# MCU.net
KiCad netlist of a schematic drawn in Altium Designer
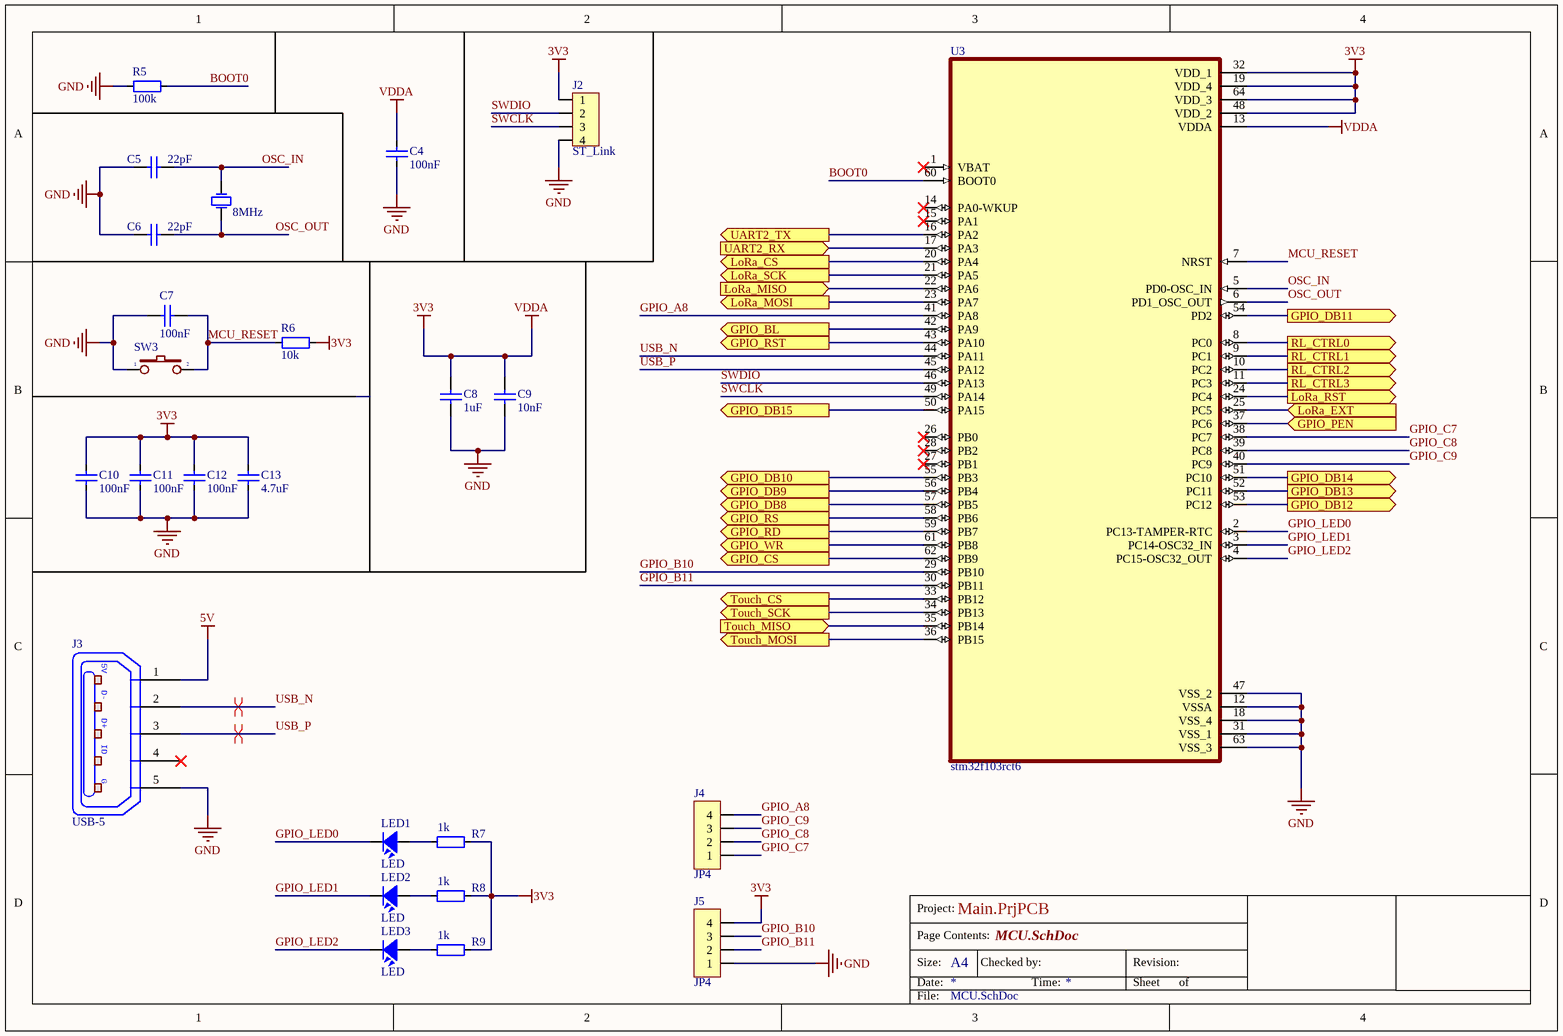
[diagram p0: MCU.SchDoc]

(export (version "E")
  (design (tool "Eeschema 10.0.6"))
  (components
    (comp (ref "C4")
      (value "100nF")
      (footprint "CAP_0805")
      (description "Capacitor")
      (fields (field (name "PUBLISHER") "Altium Limited"))
      (libsource (lib "") (part "CapSMD_1"))
    )
    (comp (ref "C5")
      (value "22pF")
      (footprint "CAP_0805")
      (description "Capacitor")
      (fields (field (name "PUBLISHER") "Altium Limited"))
      (libsource (lib "My Library") (part "CapSMD"))
    )
    (comp (ref "C6")
      (value "22pF")
      (footprint "CAP_0805")
      (description "Capacitor")
      (fields (field (name "PUBLISHER") "Altium Limited"))
      (libsource (lib "My Library") (part "CapSMD"))
    )
    (comp (ref "C7")
      (value "100nF")
      (footprint "CAP_0805")
      (description "Capacitor")
      (fields (field (name "PUBLISHER") "Altium Limited"))
      (libsource (lib "My Library") (part "CapSMD"))
    )
    (comp (ref "C8")
      (value "1uF")
      (footprint "CAP_0805")
      (description "Capacitor")
      (fields (field (name "PUBLISHER") "Altium Limited"))
      (libsource (lib "My Library") (part "CapSMD"))
    )
    (comp (ref "C9")
      (value "10nF")
      (footprint "CAP_0805")
      (description "Capacitor")
      (fields (field (name "PUBLISHER") "Altium Limited"))
      (libsource (lib "My Library") (part "CapSMD"))
    )
    (comp (ref "C10")
      (value "100nF")
      (footprint "CAP_0805")
      (description "Capacitor")
      (fields (field (name "PUBLISHER") "Altium Limited"))
      (libsource (lib "") (part "CapSMD_1"))
    )
    (comp (ref "C11")
      (value "100nF")
      (footprint "CAP_0805")
      (description "Capacitor")
      (fields (field (name "PUBLISHER") "Altium Limited"))
      (libsource (lib "") (part "CapSMD_1"))
    )
    (comp (ref "C12")
      (value "100nF")
      (footprint "CAP_0805")
      (description "Capacitor")
      (fields (field (name "PUBLISHER") "Altium Limited"))
      (libsource (lib "") (part "CapSMD_1"))
    )
    (comp (ref "C13")
      (value "4.7uF")
      (footprint "CAP_0805")
      (description "Capacitor")
      (fields (field (name "PUBLISHER") "Altium Limited"))
      (libsource (lib "") (part "CapSMD_1"))
    )
    (comp (ref "J2")
      (value "ST_Link")
      (footprint "JP4-C1T")
      (description "Header IDC, 4 x 1 Pin Vertical 2.54mm Pitch (Non-Boxed, Male)")
      (fields
        (field (name "MANUFACTURER") "Würth Elektronik eiSos GmbH")
        (field (name "PARTNO") "613002143121")
        (field (name "CREATED BY") "Karrer Zheng")
      )
      (libsource (lib "My Library") (part "Header4"))
    )
    (comp (ref "J3")
      (value "USB-5")
      (footprint "USB-M1")
      (fields
        (field (name "MANUFACTURER") "FCI")
        (field (name "MANUFACTURER PART NUMBER") "10118193-0001LF")
        (field (name ".CREATOR") "MM")
        (field (name ".CHECKED PCB") "RF")
        (field (name ".CHECKED SCH") "MM")
      )
      (libsource (lib "My Library") (part "USB-5"))
    )
    (comp (ref "J4")
      (value "JP4")
      (footprint "JP4-C1T")
      (description "WR-PHD 2.54 mm Angled Socket Header")
      (fields
        (field (name "MANUFACTURER") "Würth Elektronik eiSos GmbH")
        (field (name "PARTNO") "613004143121")
        (field (name "CREATED BY") "Karrer Zheng")
      )
      (libsource (lib "My Library") (part "JP4"))
    )
    (comp (ref "J5")
      (value "JP4")
      (footprint "JP4-C1T")
      (description "WR-PHD 2.54 mm Angled Socket Header")
      (fields
        (field (name "MANUFACTURER") "Würth Elektronik eiSos GmbH")
        (field (name "PARTNO") "613004143121")
        (field (name "CREATED BY") "Karrer Zheng")
      )
      (libsource (lib "My Library") (part "JP4"))
    )
    (comp (ref "LED1")
      (value "LED")
      (footprint "LED-0805-Red")
      (description "LED Single colour Green and Red")
      (libsource (lib "My Library") (part "LED"))
    )
    (comp (ref "LED2")
      (value "LED")
      (footprint "LED-0805-Green")
      (description "LED Single colour Green and Red")
      (libsource (lib "My Library") (part "LED"))
    )
    (comp (ref "LED3")
      (value "LED")
      (footprint "LED-0805-Blue")
      (description "LED Single colour Green and Red")
      (libsource (lib "My Library") (part "LED"))
    )
    (comp (ref "R5")
      (value "100k")
      (footprint "RES-SMD-0805")
      (description "Resistor")
      (fields
        (field (name "MANUFACTURER") "Generic Components")
        (field (name "PUBLISHER") "Altium Hobart Technology Centre")
      )
      (libsource (lib "My Library") (part "Resistor - SMD"))
    )
    (comp (ref "R6")
      (value "10k")
      (footprint "RES-SMD-0805")
      (description "Resistor")
      (fields
        (field (name "MANUFACTURER") "Generic Components")
        (field (name "PUBLISHER") "Altium Hobart Technology Centre")
      )
      (libsource (lib "My Library") (part "Resistor - SMD"))
    )
    (comp (ref "R7")
      (value "1k")
      (footprint "RES-SMD-0805")
      (description "Resistor")
      (fields
        (field (name "MANUFACTURER") "Generic Components")
        (field (name "PUBLISHER") "Altium Hobart Technology Centre")
      )
      (libsource (lib "My Library") (part "Resistor - SMD"))
    )
    (comp (ref "R8")
      (value "1k")
      (footprint "RES-SMD-0805")
      (description "Resistor")
      (fields
        (field (name "MANUFACTURER") "Generic Components")
        (field (name "PUBLISHER") "Altium Hobart Technology Centre")
      )
      (libsource (lib "My Library") (part "Resistor - SMD"))
    )
    (comp (ref "R9")
      (value "1k")
      (footprint "RES-SMD-0805")
      (description "Resistor")
      (fields
        (field (name "MANUFACTURER") "Generic Components")
        (field (name "PUBLISHER") "Altium Hobart Technology Centre")
      )
      (libsource (lib "My Library") (part "Resistor - SMD"))
    )
    (comp (ref "SW3")
      (value "SW")
      (footprint "SW2")
      (description "Switch button 2 pin")
      (libsource (lib "My Library") (part "SW2"))
    )
    (comp (ref "U3")
      (value "stm32f103rct6")
      (footprint "QFP50P1200X1200X160-64N")
      (libsource (lib "My Library") (part "stm32f103rct6"))
    )
    (comp (ref "Y1")
      (value "8MHz")
      (footprint "XTAL")
      (description "Crystal Oscillator")
      (fields (field (name "PUBLISHER") "Altium Limited"))
      (libsource (lib "My Library") (part "XTAL"))
    )
  )
  (nets
    (net (code "1") (name "/BOOT0") (class "Default")
      (node (ref "R5") (pin "1") (pinfunction "1_1") (pintype "passive"))
      (node (ref "U3") (pin "60") (pinfunction "BOOT0_60") (pintype "input"))
    )
    (net (code "2") (name "/GPIO_A8") (class "Default")
      (node (ref "J4") (pin "4") (pinfunction "4_4") (pintype "passive"))
      (node (ref "U3") (pin "41") (pinfunction "PA8_41") (pintype "bidirectional"))
    )
    (net (code "3") (name "/GPIO_B10") (class "Default")
      (node (ref "J5") (pin "3") (pinfunction "3_3") (pintype "passive"))
      (node (ref "U3") (pin "29") (pinfunction "PB10_29") (pintype "bidirectional"))
    )
    (net (code "4") (name "/GPIO_B11") (class "Default")
      (node (ref "J5") (pin "2") (pinfunction "2_2") (pintype "passive"))
      (node (ref "U3") (pin "30") (pinfunction "PB11_30") (pintype "bidirectional"))
    )
    (net (code "5") (name "/GPIO_BL") (class "Default")
      (node (ref "U3") (pin "42") (pinfunction "PA9_42") (pintype "bidirectional"))
    )
    (net (code "6") (name "/GPIO_C7") (class "Default")
      (node (ref "J4") (pin "1") (pinfunction "1_1") (pintype "passive"))
      (node (ref "U3") (pin "38") (pinfunction "PC7_38") (pintype "bidirectional"))
    )
    (net (code "7") (name "/GPIO_C8") (class "Default")
      (node (ref "J4") (pin "2") (pinfunction "2_2") (pintype "passive"))
      (node (ref "U3") (pin "39") (pinfunction "PC8_39") (pintype "bidirectional"))
    )
    (net (code "8") (name "/GPIO_C9") (class "Default")
      (node (ref "J4") (pin "3") (pinfunction "3_3") (pintype "passive"))
      (node (ref "U3") (pin "40") (pinfunction "PC9_40") (pintype "bidirectional"))
    )
    (net (code "9") (name "/GPIO_CS") (class "Default")
      (node (ref "U3") (pin "62") (pinfunction "PB9_62") (pintype "bidirectional"))
    )
    (net (code "10") (name "/GPIO_DB8") (class "Default")
      (node (ref "U3") (pin "57") (pinfunction "PB5_57") (pintype "bidirectional"))
    )
    (net (code "11") (name "/GPIO_DB9") (class "Default")
      (node (ref "U3") (pin "56") (pinfunction "PB4_56") (pintype "bidirectional"))
    )
    (net (code "12") (name "/GPIO_DB10") (class "Default")
      (node (ref "U3") (pin "55") (pinfunction "PB3_55") (pintype "bidirectional"))
    )
    (net (code "13") (name "/GPIO_DB11") (class "Default")
      (node (ref "U3") (pin "54") (pinfunction "PD2_54") (pintype "bidirectional"))
    )
    (net (code "14") (name "/GPIO_DB12") (class "Default")
      (node (ref "U3") (pin "53") (pinfunction "PC12_53") (pintype "bidirectional"))
    )
    (net (code "15") (name "/GPIO_DB13") (class "Default")
      (node (ref "U3") (pin "52") (pinfunction "PC11_52") (pintype "bidirectional"))
    )
    (net (code "16") (name "/GPIO_DB14") (class "Default")
      (node (ref "U3") (pin "51") (pinfunction "PC10_51") (pintype "bidirectional"))
    )
    (net (code "17") (name "/GPIO_DB15") (class "Default")
      (node (ref "U3") (pin "50") (pinfunction "PA15_50") (pintype "bidirectional"))
    )
    (net (code "18") (name "/GPIO_LED0") (class "Default")
      (node (ref "LED1") (pin "2") (pinfunction "2_2") (pintype "passive"))
      (node (ref "U3") (pin "2") (pinfunction "PC13-TAMPER-RTC_2") (pintype "bidirectional"))
    )
    (net (code "19") (name "/GPIO_LED1") (class "Default")
      (node (ref "LED2") (pin "2") (pinfunction "2_2") (pintype "passive"))
      (node (ref "U3") (pin "3") (pinfunction "PC14-OSC32_IN_3") (pintype "bidirectional"))
    )
    (net (code "20") (name "/GPIO_LED2") (class "Default")
      (node (ref "LED3") (pin "2") (pinfunction "2_2") (pintype "passive"))
      (node (ref "U3") (pin "4") (pinfunction "PC15-OSC32_OUT_4") (pintype "bidirectional"))
    )
    (net (code "21") (name "/GPIO_PEN") (class "Default")
      (node (ref "U3") (pin "37") (pinfunction "PC6_37") (pintype "bidirectional"))
    )
    (net (code "22") (name "/GPIO_RD") (class "Default")
      (node (ref "U3") (pin "59") (pinfunction "PB7_59") (pintype "bidirectional"))
    )
    (net (code "23") (name "/GPIO_RS") (class "Default")
      (node (ref "U3") (pin "58") (pinfunction "PB6_58") (pintype "bidirectional"))
    )
    (net (code "24") (name "/GPIO_RST") (class "Default")
      (node (ref "U3") (pin "43") (pinfunction "PA10_43") (pintype "bidirectional"))
    )
    (net (code "25") (name "/GPIO_WR") (class "Default")
      (node (ref "U3") (pin "61") (pinfunction "PB8_61") (pintype "bidirectional"))
    )
    (net (code "26") (name "/LoRa_CS") (class "Default")
      (node (ref "U3") (pin "20") (pinfunction "PA4_20") (pintype "bidirectional"))
    )
    (net (code "27") (name "/LoRa_EXT") (class "Default")
      (node (ref "U3") (pin "25") (pinfunction "PC5_25") (pintype "bidirectional"))
    )
    (net (code "28") (name "/LoRa_MISO") (class "Default")
      (node (ref "U3") (pin "22") (pinfunction "PA6_22") (pintype "bidirectional"))
    )
    (net (code "29") (name "/LoRa_MOSI") (class "Default")
      (node (ref "U3") (pin "23") (pinfunction "PA7_23") (pintype "bidirectional"))
    )
    (net (code "30") (name "/LoRa_RST") (class "Default")
      (node (ref "U3") (pin "24") (pinfunction "PC4_24") (pintype "bidirectional"))
    )
    (net (code "31") (name "/LoRa_SCK") (class "Default")
      (node (ref "U3") (pin "21") (pinfunction "PA5_21") (pintype "bidirectional"))
    )
    (net (code "32") (name "/MCU_RESET") (class "Default")
      (node (ref "C7") (pin "2") (pinfunction "2_2") (pintype "passive"))
      (node (ref "R6") (pin "2") (pinfunction "2_2") (pintype "passive"))
      (node (ref "SW3") (pin "2") (pinfunction "2_2") (pintype "passive"))
      (node (ref "U3") (pin "7") (pinfunction "NRST_7") (pintype "input"))
    )
    (net (code "33") (name "/OSC_IN") (class "Default")
      (node (ref "C5") (pin "2") (pinfunction "2_2") (pintype "passive"))
      (node (ref "U3") (pin "5") (pinfunction "PD0-OSC_IN_5") (pintype "input"))
      (node (ref "Y1") (pin "1") (pinfunction "OSC1_1") (pintype "passive"))
    )
    (net (code "34") (name "/OSC_OUT") (class "Default")
      (node (ref "C6") (pin "2") (pinfunction "2_2") (pintype "passive"))
      (node (ref "U3") (pin "6") (pinfunction "PD1_OSC_OUT_6") (pintype "output"))
      (node (ref "Y1") (pin "2") (pinfunction "OSC2_2") (pintype "passive"))
    )
    (net (code "35") (name "/RL_CTRL0") (class "Default")
      (node (ref "U3") (pin "8") (pinfunction "PC0_8") (pintype "bidirectional"))
    )
    (net (code "36") (name "/RL_CTRL1") (class "Default")
      (node (ref "U3") (pin "9") (pinfunction "PC1_9") (pintype "bidirectional"))
    )
    (net (code "37") (name "/RL_CTRL2") (class "Default")
      (node (ref "U3") (pin "10") (pinfunction "PC2_10") (pintype "bidirectional"))
    )
    (net (code "38") (name "/RL_CTRL3") (class "Default")
      (node (ref "U3") (pin "11") (pinfunction "PC3_11") (pintype "bidirectional"))
    )
    (net (code "39") (name "/SWCLK") (class "Default")
      (node (ref "J2") (pin "3") (pinfunction "3_3") (pintype "passive"))
      (node (ref "U3") (pin "49") (pinfunction "PA14_49") (pintype "bidirectional"))
    )
    (net (code "40") (name "/SWDIO") (class "Default")
      (node (ref "J2") (pin "2") (pinfunction "2_2") (pintype "passive"))
      (node (ref "U3") (pin "46") (pinfunction "PA13_46") (pintype "bidirectional"))
    )
    (net (code "41") (name "/Touch_CS") (class "Default")
      (node (ref "U3") (pin "33") (pinfunction "PB12_33") (pintype "bidirectional"))
    )
    (net (code "42") (name "/Touch_MISO") (class "Default")
      (node (ref "U3") (pin "35") (pinfunction "PB14_35") (pintype "bidirectional"))
    )
    (net (code "43") (name "/Touch_MOSI") (class "Default")
      (node (ref "U3") (pin "36") (pinfunction "PB15_36") (pintype "bidirectional"))
    )
    (net (code "44") (name "/Touch_SCK") (class "Default")
      (node (ref "U3") (pin "34") (pinfunction "PB13_34") (pintype "bidirectional"))
    )
    (net (code "45") (name "/UART2_RX") (class "Default")
      (node (ref "U3") (pin "17") (pinfunction "PA3_17") (pintype "bidirectional"))
    )
    (net (code "46") (name "/UART2_TX") (class "Default")
      (node (ref "U3") (pin "16") (pinfunction "PA2_16") (pintype "bidirectional"))
    )
    (net (code "47") (name "/USB_N") (class "Default")
      (node (ref "J3") (pin "2") (pinfunction "P2_2") (pintype "passive"))
      (node (ref "U3") (pin "44") (pinfunction "PA11_44") (pintype "bidirectional"))
    )
    (net (code "48") (name "/USB_P") (class "Default")
      (node (ref "J3") (pin "3") (pinfunction "P3_3") (pintype "passive"))
      (node (ref "U3") (pin "45") (pinfunction "PA12_45") (pintype "bidirectional"))
    )
    (net (code "49") (name "3V3") (class "Default")
      (node (ref "C10") (pin "2") (pinfunction "2_2") (pintype "passive"))
      (node (ref "C11") (pin "2") (pinfunction "2_2") (pintype "passive"))
      (node (ref "C12") (pin "2") (pinfunction "2_2") (pintype "passive"))
      (node (ref "C13") (pin "2") (pinfunction "2_2") (pintype "passive"))
      (node (ref "C4") (pin "2") (pinfunction "2_2") (pintype "passive"))
      (node (ref "C8") (pin "2") (pinfunction "2_2") (pintype "passive"))
      (node (ref "C9") (pin "2") (pinfunction "2_2") (pintype "passive"))
      (node (ref "J2") (pin "1") (pinfunction "1_1") (pintype "passive"))
      (node (ref "J5") (pin "4") (pinfunction "4_4") (pintype "passive"))
      (node (ref "R6") (pin "1") (pinfunction "1_1") (pintype "passive"))
      (node (ref "R7") (pin "1") (pinfunction "1_1") (pintype "passive"))
      (node (ref "R8") (pin "1") (pinfunction "1_1") (pintype "passive"))
      (node (ref "R9") (pin "1") (pinfunction "1_1") (pintype "passive"))
      (node (ref "U3") (pin "13") (pinfunction "VDDA_13") (pintype "power_in"))
      (node (ref "U3") (pin "19") (pinfunction "VDD_4_19") (pintype "power_in"))
      (node (ref "U3") (pin "32") (pinfunction "VDD_1_32") (pintype "power_in"))
      (node (ref "U3") (pin "48") (pinfunction "VDD_2_48") (pintype "power_in"))
      (node (ref "U3") (pin "64") (pinfunction "VDD_3_64") (pintype "power_in"))
    )
    (net (code "50") (name "5V") (class "Default")
      (node (ref "J3") (pin "1") (pinfunction "P1_1") (pintype "passive"))
    )
    (net (code "51") (name "GND") (class "Default")
      (node (ref "C10") (pin "1") (pinfunction "1_1") (pintype "passive"))
      (node (ref "C11") (pin "1") (pinfunction "1_1") (pintype "passive"))
      (node (ref "C12") (pin "1") (pinfunction "1_1") (pintype "passive"))
      (node (ref "C13") (pin "1") (pinfunction "1_1") (pintype "passive"))
      (node (ref "C4") (pin "1") (pinfunction "1_1") (pintype "passive"))
      (node (ref "C5") (pin "1") (pinfunction "1_1") (pintype "passive"))
      (node (ref "C6") (pin "1") (pinfunction "1_1") (pintype "passive"))
      (node (ref "C7") (pin "1") (pinfunction "1_1") (pintype "passive"))
      (node (ref "C8") (pin "1") (pinfunction "1_1") (pintype "passive"))
      (node (ref "C9") (pin "1") (pinfunction "1_1") (pintype "passive"))
      (node (ref "J2") (pin "4") (pinfunction "4_4") (pintype "passive"))
      (node (ref "J3") (pin "5") (pinfunction "P5_5") (pintype "passive"))
      (node (ref "J5") (pin "1") (pinfunction "1_1") (pintype "passive"))
      (node (ref "R5") (pin "2") (pinfunction "2_2") (pintype "passive"))
      (node (ref "SW3") (pin "1") (pinfunction "1_1") (pintype "passive"))
      (node (ref "U3") (pin "12") (pinfunction "VSSA_12") (pintype "power_in"))
      (node (ref "U3") (pin "18") (pinfunction "VSS_4_18") (pintype "power_in"))
      (node (ref "U3") (pin "31") (pinfunction "VSS_1_31") (pintype "power_in"))
      (node (ref "U3") (pin "47") (pinfunction "VSS_2_47") (pintype "power_in"))
      (node (ref "U3") (pin "63") (pinfunction "VSS_3_63") (pintype "power_in"))
    )
    (net (code "52") (name "Net-(LED1-Pad1)") (class "Default")
      (node (ref "LED1") (pin "1") (pinfunction "1_1") (pintype "passive"))
      (node (ref "R7") (pin "2") (pinfunction "2_2") (pintype "passive"))
    )
    (net (code "53") (name "Net-(LED2-Pad1)") (class "Default")
      (node (ref "LED2") (pin "1") (pinfunction "1_1") (pintype "passive"))
      (node (ref "R8") (pin "2") (pinfunction "2_2") (pintype "passive"))
    )
    (net (code "54") (name "Net-(LED3-Pad1)") (class "Default")
      (node (ref "LED3") (pin "1") (pinfunction "1_1") (pintype "passive"))
      (node (ref "R9") (pin "2") (pinfunction "2_2") (pintype "passive"))
    )
    (net (code "55") (name "unconnected-(J3-P4-Pad4)") (class "Default")
      (node (ref "J3") (pin "4") (pinfunction "P4_4") (pintype "passive+no_connect"))
    )
    (net (code "56") (name "unconnected-(U3-PA0-WKUP-Pad14)") (class "Default")
      (node (ref "U3") (pin "14") (pinfunction "PA0-WKUP_14") (pintype "bidirectional+no_connect"))
    )
    (net (code "57") (name "unconnected-(U3-PA1-Pad15)") (class "Default")
      (node (ref "U3") (pin "15") (pinfunction "PA1_15") (pintype "bidirectional+no_connect"))
    )
    (net (code "58") (name "unconnected-(U3-PB0-Pad26)") (class "Default")
      (node (ref "U3") (pin "26") (pinfunction "PB0_26") (pintype "bidirectional+no_connect"))
    )
    (net (code "59") (name "unconnected-(U3-PB1-Pad27)") (class "Default")
      (node (ref "U3") (pin "27") (pinfunction "PB1_27") (pintype "bidirectional+no_connect"))
    )
    (net (code "60") (name "unconnected-(U3-PB2-Pad28)") (class "Default")
      (node (ref "U3") (pin "28") (pinfunction "PB2_28") (pintype "bidirectional+no_connect"))
    )
    (net (code "61") (name "unconnected-(U3-VBAT-Pad1)") (class "Default")
      (node (ref "U3") (pin "1") (pinfunction "VBAT_1") (pintype "input+no_connect"))
    )
  )
)
